# k1fm-pico-balloon-v1_3.net
KiCad netlist of a schematic drawn in EAGLE
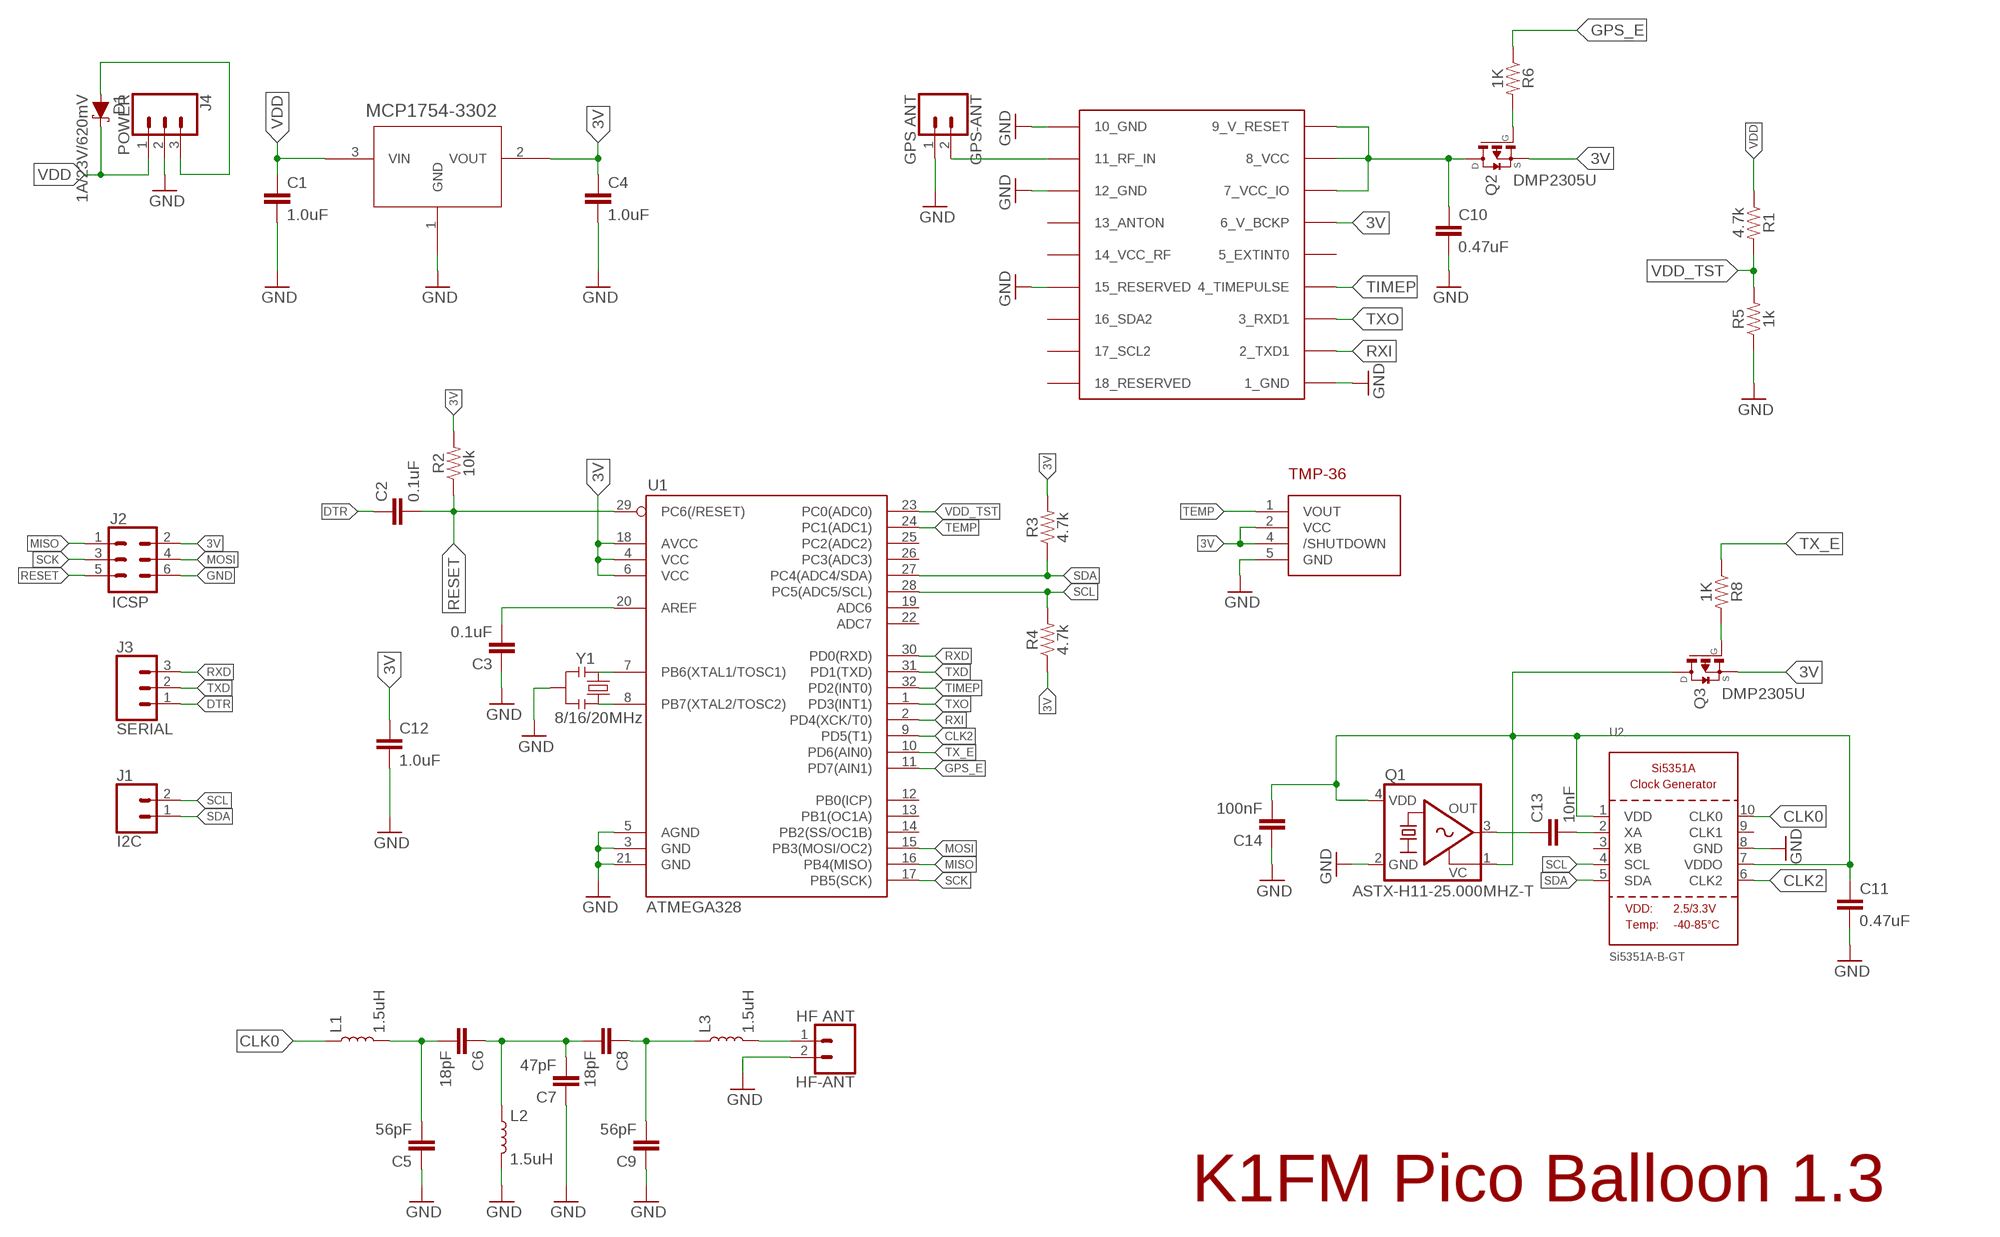
[diagram p0: schematic, sheet 1]

(export (version "E")
  (design (tool "Eeschema 10.0.6"))
  (components
    (comp (ref "C1")
      (value "1.0uF")
      (footprint "eagle-import:0603")
      (libsource (lib "eagle-import") (part "1.0UF-0603-16V-10%"))
    )
    (comp (ref "C2")
      (value "0.1uF")
      (footprint "eagle-import:0603")
      (libsource (lib "eagle-import") (part "0.1UF-0603-25V-5%"))
    )
    (comp (ref "C3")
      (value "0.1uF")
      (footprint "eagle-import:0603")
      (libsource (lib "eagle-import") (part "0.1UF-0603-25V-5%"))
    )
    (comp (ref "C4")
      (value "1.0uF")
      (footprint "eagle-import:0603")
      (libsource (lib "eagle-import") (part "1.0UF-0603-16V-10%"))
    )
    (comp (ref "C5")
      (value "56pF")
      (footprint "eagle-import:0603")
      (libsource (lib "eagle-import") (part "0.1UF-0603-25V-5%"))
    )
    (comp (ref "C6")
      (value "18pF")
      (footprint "eagle-import:0603")
      (libsource (lib "eagle-import") (part "0.1UF-0603-25V-5%"))
    )
    (comp (ref "C7")
      (value "47pF")
      (footprint "eagle-import:0603")
      (libsource (lib "eagle-import") (part "0.1UF-0603-25V-5%"))
    )
    (comp (ref "C8")
      (value "18pF")
      (footprint "eagle-import:0603")
      (libsource (lib "eagle-import") (part "0.1UF-0603-25V-5%"))
    )
    (comp (ref "C9")
      (value "56pF")
      (footprint "eagle-import:0603")
      (libsource (lib "eagle-import") (part "0.1UF-0603-25V-5%"))
    )
    (comp (ref "C10")
      (value "0.47uF")
      (footprint "eagle-import:0603")
      (libsource (lib "eagle-import") (part "0.1UF-0603-25V-5%"))
    )
    (comp (ref "C11")
      (value "0.47uF")
      (footprint "eagle-import:0603")
      (libsource (lib "eagle-import") (part "0.1UF-0603-25V-5%"))
    )
    (comp (ref "C12")
      (value "1.0uF")
      (footprint "eagle-import:0603")
      (libsource (lib "eagle-import") (part "1.0UF-0603-16V-10%"))
    )
    (comp (ref "C13")
      (value "10nF")
      (footprint "eagle-import:0603")
      (libsource (lib "eagle-import") (part "10NF-0603-50V-10%"))
    )
    (comp (ref "C14")
      (value "100nF")
      (footprint "eagle-import:0603")
      (libsource (lib "eagle-import") (part "10NF-0603-50V-10%"))
    )
    (comp (ref "D1")
      (value "1A/23V/620mV")
      (footprint "eagle-import:SOD-323")
      (libsource (lib "eagle-import") (part "DIODE-SCHOTTKY-BAT20J"))
    )
    (comp (ref "GPS-ANT")
      (value "GPS ANT")
      (footprint "eagle-import:1X02")
      (libsource (lib "eagle-import") (part "CONN_02"))
    )
    (comp (ref "GPS1")
      (value "UBLOX_MAX")
      (footprint "eagle-import:UBLOX_MAX")
      (libsource (lib "eagle-import") (part "UBLOX_MAX"))
    )
    (comp (ref "HF-ANT")
      (value "HF ANT")
      (footprint "eagle-import:1X02")
      (libsource (lib "eagle-import") (part "CONN_02"))
    )
    (comp (ref "J1")
      (value "I2C")
      (footprint "eagle-import:1X02")
      (libsource (lib "eagle-import") (part "CONN_02"))
    )
    (comp (ref "J2")
      (value "ICSP")
      (footprint "eagle-import:2X3")
      (libsource (lib "eagle-import") (part "CONN_03X2FEMALE"))
    )
    (comp (ref "J3")
      (value "SERIAL")
      (footprint "eagle-import:1X03")
      (libsource (lib "eagle-import") (part "CONN_03"))
    )
    (comp (ref "J4")
      (value "POWER")
      (footprint "eagle-import:1X03")
      (libsource (lib "eagle-import") (part "CONN_03"))
    )
    (comp (ref "L1")
      (value "1.5uH")
      (footprint "eagle-import:0603")
      (libsource (lib "eagle-import") (part "INDUCTOR-0603-33NH"))
    )
    (comp (ref "L2")
      (value "1.5uH")
      (footprint "eagle-import:0603")
      (libsource (lib "eagle-import") (part "INDUCTOR-0603-33NH"))
    )
    (comp (ref "L3")
      (value "1.5uH")
      (footprint "eagle-import:0603")
      (libsource (lib "eagle-import") (part "INDUCTOR-0603-33NH"))
    )
    (comp (ref "Q1")
      (value "ASTX-H11-25.000MHZ-T")
      (footprint "eagle-import:3.2X2.5_KXO-84")
      (libsource (lib "eagle-import") (part "KXO-VCXO-SINE-84"))
    )
    (comp (ref "Q2")
      (value "DMP2305U")
      (footprint "eagle-import:SOT23")
      (libsource (lib "eagle-import") (part "DMP2305U"))
    )
    (comp (ref "Q3")
      (value "DMP2305U")
      (footprint "eagle-import:SOT23")
      (libsource (lib "eagle-import") (part "DMP2305U"))
    )
    (comp (ref "R1")
      (value "4.7k")
      (footprint "eagle-import:0603")
      (libsource (lib "eagle-import") (part "10KOHM-0603-1/10W-1%"))
    )
    (comp (ref "R2")
      (value "10k")
      (footprint "eagle-import:0603")
      (libsource (lib "eagle-import") (part "10KOHM-0603-1/10W-1%"))
    )
    (comp (ref "R3")
      (value "4.7k")
      (footprint "eagle-import:0603")
      (libsource (lib "eagle-import") (part "4.7KOHM-0603-1/10W-1%"))
    )
    (comp (ref "R4")
      (value "4.7k")
      (footprint "eagle-import:0603")
      (libsource (lib "eagle-import") (part "4.7KOHM-0603-1/10W-1%"))
    )
    (comp (ref "R5")
      (value "1k")
      (footprint "eagle-import:0603")
      (libsource (lib "eagle-import") (part "10KOHM-0603-1/10W-1%"))
    )
    (comp (ref "R6")
      (value "1K")
      (footprint "eagle-import:0603")
      (libsource (lib "eagle-import") (part "10KOHM-0603-1/10W-1%"))
    )
    (comp (ref "R8")
      (value "1K")
      (footprint "eagle-import:0603")
      (libsource (lib "eagle-import") (part "10KOHM-0603-1/10W-1%"))
    )
    (comp (ref "U1")
      (value "ATMEGA328")
      (footprint "eagle-import:TQFP32-08")
      (libsource (lib "eagle-import") (part "ATMEGA168"))
    )
    (comp (ref "U2")
      (value "Si5351A-B-GT")
      (footprint "eagle-import:MSOP10")
      (libsource (lib "eagle-import") (part "SI5351A"))
    )
    (comp (ref "U3")
      (value "MCP1754X-XXXXX/C")
      (footprint "eagle-import:SOT-23A_MC")
      (libsource (lib "eagle-import") (part "MCP1754X-XXXXX/C"))
    )
    (comp (ref "U4")
      (value "TMP36")
      (footprint "eagle-import:SOT-23")
      (libsource (lib "eagle-import") (part "TMP36"))
    )
    (comp (ref "Y1")
      (value "8/16/20MHz")
      (footprint "eagle-import:RESONATOR-SMD-1_1")
      (libsource (lib "eagle-import") (part "RESONATOR1{colon}1"))
    )
  )
  (nets
    (net (code "1") (name "3V") (class "Default")
      (node (ref "C12") (pin "1") (pinfunction "1_1") (pintype "passive"))
      (node (ref "C4") (pin "1") (pinfunction "1_1") (pintype "passive"))
      (node (ref "GPS1") (pin "6_V_BCKP") (pinfunction "6_V_BCKP_6_V_BCKP") (pintype "bidirectional"))
      (node (ref "J2") (pin "2") (pinfunction "2_2") (pintype "bidirectional"))
      (node (ref "Q2") (pin "2") (pinfunction "S_2") (pintype "passive"))
      (node (ref "Q3") (pin "2") (pinfunction "S_2") (pintype "passive"))
      (node (ref "R2") (pin "2") (pinfunction "2_2") (pintype "passive"))
      (node (ref "R3") (pin "2") (pinfunction "2_2") (pintype "passive"))
      (node (ref "R4") (pin "1") (pinfunction "1_1") (pintype "passive"))
      (node (ref "U1") (pin "18") (pinfunction "AVCC_18") (pintype "bidirectional"))
      (node (ref "U1") (pin "4") (pinfunction "VCC_4") (pintype "bidirectional"))
      (node (ref "U1") (pin "6") (pinfunction "VCC_6") (pintype "bidirectional"))
      (node (ref "U3") (pin "2") (pinfunction "VOUT_2") (pintype "passive"))
      (node (ref "U4") (pin "2") (pinfunction "VCC_2") (pintype "bidirectional"))
      (node (ref "U4") (pin "4") (pinfunction "/SHUTDOWN_4") (pintype "bidirectional"))
    )
    (net (code "2") (name "CLK0") (class "Default")
      (node (ref "L1") (pin "1") (pinfunction "1_1") (pintype "passive"))
      (node (ref "U2") (pin "10") (pinfunction "CLK0_10") (pintype "output"))
    )
    (net (code "3") (name "CLK2") (class "Default")
      (node (ref "U1") (pin "9") (pinfunction "PD5(T1)_9") (pintype "bidirectional"))
      (node (ref "U2") (pin "6") (pinfunction "CLK2_6") (pintype "output"))
    )
    (net (code "4") (name "DTR") (class "Default")
      (node (ref "C2") (pin "1") (pinfunction "1_1") (pintype "passive"))
      (node (ref "J3") (pin "1") (pinfunction "1_1") (pintype "passive"))
    )
    (net (code "5") (name "GND") (class "Default")
      (node (ref "C1") (pin "2") (pinfunction "2_2") (pintype "passive"))
      (node (ref "C10") (pin "2") (pinfunction "2_2") (pintype "passive"))
      (node (ref "C11") (pin "2") (pinfunction "2_2") (pintype "passive"))
      (node (ref "C12") (pin "2") (pinfunction "2_2") (pintype "passive"))
      (node (ref "C14") (pin "1") (pinfunction "1_1") (pintype "passive"))
      (node (ref "C3") (pin "1") (pinfunction "1_1") (pintype "passive"))
      (node (ref "C4") (pin "2") (pinfunction "2_2") (pintype "passive"))
      (node (ref "C5") (pin "1") (pinfunction "1_1") (pintype "passive"))
      (node (ref "C7") (pin "1") (pinfunction "1_1") (pintype "passive"))
      (node (ref "C9") (pin "1") (pinfunction "1_1") (pintype "passive"))
      (node (ref "GPS-ANT") (pin "1") (pinfunction "1_1") (pintype "passive"))
      (node (ref "GPS1") (pin "10_GND") (pinfunction "10_GND_10_GND") (pintype "power_in"))
      (node (ref "GPS1") (pin "12_GND") (pinfunction "12_GND_12_GND") (pintype "power_in"))
      (node (ref "GPS1") (pin "15_RESERVED") (pinfunction "15_RESERVED_15_RESERVED") (pintype "bidirectional"))
      (node (ref "GPS1") (pin "1_GND") (pinfunction "1_GND_1_GND") (pintype "power_in"))
      (node (ref "HF-ANT") (pin "2") (pinfunction "2_2") (pintype "passive"))
      (node (ref "J2") (pin "6") (pinfunction "6_6") (pintype "bidirectional"))
      (node (ref "J4") (pin "2") (pinfunction "2_2") (pintype "passive"))
      (node (ref "L2") (pin "2") (pinfunction "2_2") (pintype "passive"))
      (node (ref "Q1") (pin "2") (pinfunction "GND_2") (pintype "power_in"))
      (node (ref "R5") (pin "1") (pinfunction "1_1") (pintype "passive"))
      (node (ref "U1") (pin "21") (pinfunction "GND_21") (pintype "bidirectional"))
      (node (ref "U1") (pin "3") (pinfunction "GND_3") (pintype "bidirectional"))
      (node (ref "U1") (pin "5") (pinfunction "AGND_5") (pintype "bidirectional"))
      (node (ref "U2") (pin "8") (pinfunction "GND_8") (pintype "power_in"))
      (node (ref "U3") (pin "1") (pinfunction "GND_1") (pintype "passive"))
      (node (ref "U4") (pin "5") (pinfunction "GND_5") (pintype "bidirectional"))
      (node (ref "Y1") (pin "2") (pinfunction "2_2") (pintype "passive"))
    )
    (net (code "6") (name "GPS_E") (class "Default")
      (node (ref "R6") (pin "1") (pinfunction "1_1") (pintype "passive"))
      (node (ref "U1") (pin "11") (pinfunction "PD7(AIN1)_11") (pintype "bidirectional"))
    )
    (net (code "7") (name "MISO") (class "Default")
      (node (ref "J2") (pin "1") (pinfunction "1_1") (pintype "bidirectional"))
      (node (ref "U1") (pin "16") (pinfunction "PB4(MISO)_16") (pintype "bidirectional"))
    )
    (net (code "8") (name "MOSI") (class "Default")
      (node (ref "J2") (pin "4") (pinfunction "4_4") (pintype "bidirectional"))
      (node (ref "U1") (pin "15") (pinfunction "PB3(MOSI/OC2)_15") (pintype "bidirectional"))
    )
    (net (code "9") (name "Net-(C5-Pad2)") (class "Default")
      (node (ref "C5") (pin "2") (pinfunction "2_2") (pintype "passive"))
      (node (ref "C6") (pin "2") (pinfunction "2_2") (pintype "passive"))
      (node (ref "L1") (pin "2") (pinfunction "2_2") (pintype "passive"))
    )
    (net (code "10") (name "Net-(C6-Pad1)") (class "Default")
      (node (ref "C6") (pin "1") (pinfunction "1_1") (pintype "passive"))
      (node (ref "C7") (pin "2") (pinfunction "2_2") (pintype "passive"))
      (node (ref "C8") (pin "2") (pinfunction "2_2") (pintype "passive"))
      (node (ref "L2") (pin "1") (pinfunction "1_1") (pintype "passive"))
    )
    (net (code "11") (name "Net-(C8-Pad1)") (class "Default")
      (node (ref "C8") (pin "1") (pinfunction "1_1") (pintype "passive"))
      (node (ref "C9") (pin "2") (pinfunction "2_2") (pintype "passive"))
      (node (ref "L3") (pin "1") (pinfunction "1_1") (pintype "passive"))
    )
    (net (code "12") (name "Net-(D1-PadA)") (class "Default")
      (node (ref "D1") (pin "A") (pinfunction "A_A") (pintype "passive"))
      (node (ref "J4") (pin "3") (pinfunction "3_3") (pintype "passive"))
    )
    (net (code "13") (name "Net-(GPS-ANT-Pad2)") (class "Default")
      (node (ref "GPS-ANT") (pin "2") (pinfunction "2_2") (pintype "passive"))
      (node (ref "GPS1") (pin "11_RF_IN") (pinfunction "11_RF_IN_11_RF_IN") (pintype "bidirectional"))
    )
    (net (code "14") (name "Net-(HF-ANT-Pad1)") (class "Default")
      (node (ref "HF-ANT") (pin "1") (pinfunction "1_1") (pintype "passive"))
      (node (ref "L3") (pin "2") (pinfunction "2_2") (pintype "passive"))
    )
    (net (code "15") (name "Net-(Q1-OUT)") (class "Default")
      (node (ref "C13") (pin "1") (pinfunction "1_1") (pintype "passive"))
      (node (ref "Q1") (pin "3") (pinfunction "OUT_3") (pintype "output"))
    )
    (net (code "16") (name "Net-(Q1-VC)") (class "Default")
      (node (ref "C11") (pin "1") (pinfunction "1_1") (pintype "passive"))
      (node (ref "C14") (pin "2") (pinfunction "2_2") (pintype "passive"))
      (node (ref "Q1") (pin "1") (pinfunction "VC_1") (pintype "input"))
      (node (ref "Q1") (pin "4") (pinfunction "VDD_4") (pintype "power_in"))
      (node (ref "Q3") (pin "3") (pinfunction "D_3") (pintype "passive"))
      (node (ref "U2") (pin "1") (pinfunction "VDD_1") (pintype "power_in"))
      (node (ref "U2") (pin "7") (pinfunction "VDDO_7") (pintype "power_in"))
    )
    (net (code "17") (name "Net-(Q2-D)") (class "Default")
      (node (ref "C10") (pin "1") (pinfunction "1_1") (pintype "passive"))
      (node (ref "GPS1") (pin "7_VCC_IO") (pinfunction "7_VCC_IO_7_VCC_IO") (pintype "power_in"))
      (node (ref "GPS1") (pin "8_VCC") (pinfunction "8_VCC_8_VCC") (pintype "power_in"))
      (node (ref "GPS1") (pin "9_V_RESET") (pinfunction "9_V_RESET_9_V_RESET") (pintype "power_in"))
      (node (ref "Q2") (pin "3") (pinfunction "D_3") (pintype "passive"))
    )
    (net (code "18") (name "Net-(Q2-G)") (class "Default")
      (node (ref "Q2") (pin "1") (pinfunction "G_1") (pintype "passive"))
      (node (ref "R6") (pin "2") (pinfunction "2_2") (pintype "passive"))
    )
    (net (code "19") (name "Net-(Q3-G)") (class "Default")
      (node (ref "Q3") (pin "1") (pinfunction "G_1") (pintype "passive"))
      (node (ref "R8") (pin "2") (pinfunction "2_2") (pintype "passive"))
    )
    (net (code "20") (name "Net-(U1-AREF)") (class "Default")
      (node (ref "C3") (pin "2") (pinfunction "2_2") (pintype "passive"))
      (node (ref "U1") (pin "20") (pinfunction "AREF_20") (pintype "bidirectional"))
    )
    (net (code "21") (name "Net-(U1-PB6(XTAL1{slash}TOSC1))") (class "Default")
      (node (ref "U1") (pin "7") (pinfunction "PB6(XTAL1/TOSC1)_7") (pintype "bidirectional"))
      (node (ref "Y1") (pin "1") (pinfunction "1_1") (pintype "passive"))
    )
    (net (code "22") (name "Net-(U1-PB7(XTAL2{slash}TOSC2))") (class "Default")
      (node (ref "U1") (pin "8") (pinfunction "PB7(XTAL2/TOSC2)_8") (pintype "bidirectional"))
      (node (ref "Y1") (pin "3") (pinfunction "3_3") (pintype "passive"))
    )
    (net (code "23") (name "Net-(U2-XA)") (class "Default")
      (node (ref "C13") (pin "2") (pinfunction "2_2") (pintype "passive"))
      (node (ref "U2") (pin "2") (pinfunction "XA_2") (pintype "input"))
    )
    (net (code "24") (name "RESET") (class "Default")
      (node (ref "C2") (pin "2") (pinfunction "2_2") (pintype "passive"))
      (node (ref "J2") (pin "5") (pinfunction "5_5") (pintype "bidirectional"))
      (node (ref "R2") (pin "1") (pinfunction "1_1") (pintype "passive"))
      (node (ref "U1") (pin "29") (pinfunction "PC6(/RESET)_29") (pintype "bidirectional"))
    )
    (net (code "25") (name "RXD") (class "Default")
      (node (ref "J3") (pin "3") (pinfunction "3_3") (pintype "passive"))
      (node (ref "U1") (pin "30") (pinfunction "PD0(RXD)_30") (pintype "bidirectional"))
    )
    (net (code "26") (name "RXI") (class "Default")
      (node (ref "GPS1") (pin "2_TXD1") (pinfunction "2_TXD1_2_TXD1") (pintype "bidirectional"))
      (node (ref "U1") (pin "2") (pinfunction "PD4(XCK/T0)_2") (pintype "bidirectional"))
    )
    (net (code "27") (name "SCK") (class "Default")
      (node (ref "J2") (pin "3") (pinfunction "3_3") (pintype "bidirectional"))
      (node (ref "U1") (pin "17") (pinfunction "PB5(SCK)_17") (pintype "bidirectional"))
    )
    (net (code "28") (name "SCL") (class "Default")
      (node (ref "J1") (pin "2") (pinfunction "2_2") (pintype "passive"))
      (node (ref "R4") (pin "2") (pinfunction "2_2") (pintype "passive"))
      (node (ref "U1") (pin "28") (pinfunction "PC5(ADC5/SCL)_28") (pintype "bidirectional"))
      (node (ref "U2") (pin "4") (pinfunction "SCL_4") (pintype "input"))
    )
    (net (code "29") (name "SDA") (class "Default")
      (node (ref "J1") (pin "1") (pinfunction "1_1") (pintype "passive"))
      (node (ref "R3") (pin "1") (pinfunction "1_1") (pintype "passive"))
      (node (ref "U1") (pin "27") (pinfunction "PC4(ADC4/SDA)_27") (pintype "bidirectional"))
      (node (ref "U2") (pin "5") (pinfunction "SDA_5") (pintype "bidirectional"))
    )
    (net (code "30") (name "TEMP") (class "Default")
      (node (ref "U1") (pin "24") (pinfunction "PC1(ADC1)_24") (pintype "bidirectional"))
      (node (ref "U4") (pin "1") (pinfunction "VOUT_1") (pintype "bidirectional"))
    )
    (net (code "31") (name "TIMEP") (class "Default")
      (node (ref "GPS1") (pin "4_TIMEPULSE") (pinfunction "4_TIMEPULSE_4_TIMEPULSE") (pintype "bidirectional"))
      (node (ref "U1") (pin "32") (pinfunction "PD2(INT0)_32") (pintype "bidirectional"))
    )
    (net (code "32") (name "TXD") (class "Default")
      (node (ref "J3") (pin "2") (pinfunction "2_2") (pintype "passive"))
      (node (ref "U1") (pin "31") (pinfunction "PD1(TXD)_31") (pintype "bidirectional"))
    )
    (net (code "33") (name "TXO") (class "Default")
      (node (ref "GPS1") (pin "3_RXD1") (pinfunction "3_RXD1_3_RXD1") (pintype "bidirectional"))
      (node (ref "U1") (pin "1") (pinfunction "PD3(INT1)_1") (pintype "bidirectional"))
    )
    (net (code "34") (name "TX_E") (class "Default")
      (node (ref "R8") (pin "1") (pinfunction "1_1") (pintype "passive"))
      (node (ref "U1") (pin "10") (pinfunction "PD6(AIN0)_10") (pintype "bidirectional"))
    )
    (net (code "35") (name "VDD") (class "Default")
      (node (ref "C1") (pin "1") (pinfunction "1_1") (pintype "passive"))
      (node (ref "D1") (pin "C") (pinfunction "C_C") (pintype "passive"))
      (node (ref "J4") (pin "1") (pinfunction "1_1") (pintype "passive"))
      (node (ref "R1") (pin "1") (pinfunction "1_1") (pintype "passive"))
      (node (ref "U3") (pin "3") (pinfunction "VIN_3") (pintype "passive"))
    )
    (net (code "36") (name "VDD_TST") (class "Default")
      (node (ref "R1") (pin "2") (pinfunction "2_2") (pintype "passive"))
      (node (ref "R5") (pin "2") (pinfunction "2_2") (pintype "passive"))
      (node (ref "U1") (pin "23") (pinfunction "PC0(ADC0)_23") (pintype "bidirectional"))
    )
    (net (code "37") (name "unconnected-(GPS1-Pad5_EXTINT0)") (class "Default")
      (node (ref "GPS1") (pin "5_EXTINT0") (pinfunction "5_EXTINT0_5_EXTINT0") (pintype "bidirectional"))
    )
    (net (code "38") (name "unconnected-(GPS1-Pad13_ANTON)") (class "Default")
      (node (ref "GPS1") (pin "13_ANTON") (pinfunction "13_ANTON_13_ANTON") (pintype "bidirectional"))
    )
    (net (code "39") (name "unconnected-(GPS1-Pad14_VCC_RF)") (class "Default")
      (node (ref "GPS1") (pin "14_VCC_RF") (pinfunction "14_VCC_RF_14_VCC_RF") (pintype "bidirectional"))
    )
    (net (code "40") (name "unconnected-(GPS1-Pad16_SDA2)") (class "Default")
      (node (ref "GPS1") (pin "16_SDA2") (pinfunction "16_SDA2_16_SDA2") (pintype "bidirectional"))
    )
    (net (code "41") (name "unconnected-(GPS1-Pad17_SCL2)") (class "Default")
      (node (ref "GPS1") (pin "17_SCL2") (pinfunction "17_SCL2_17_SCL2") (pintype "bidirectional"))
    )
    (net (code "42") (name "unconnected-(GPS1-Pad18_RESERVED)") (class "Default")
      (node (ref "GPS1") (pin "18_RESERVED") (pinfunction "18_RESERVED_18_RESERVED") (pintype "bidirectional"))
    )
    (net (code "43") (name "unconnected-(U1-ADC6-Pad19)") (class "Default")
      (node (ref "U1") (pin "19") (pinfunction "ADC6_19") (pintype "bidirectional"))
    )
    (net (code "44") (name "unconnected-(U1-ADC7-Pad22)") (class "Default")
      (node (ref "U1") (pin "22") (pinfunction "ADC7_22") (pintype "bidirectional"))
    )
    (net (code "45") (name "unconnected-(U1-PB0(ICP)-Pad12)") (class "Default")
      (node (ref "U1") (pin "12") (pinfunction "PB0(ICP)_12") (pintype "bidirectional"))
    )
    (net (code "46") (name "unconnected-(U1-PB1(OC1A)-Pad13)") (class "Default")
      (node (ref "U1") (pin "13") (pinfunction "PB1(OC1A)_13") (pintype "bidirectional"))
    )
    (net (code "47") (name "unconnected-(U1-PB2(SS{slash}OC1B)-Pad14)") (class "Default")
      (node (ref "U1") (pin "14") (pinfunction "PB2(SS/OC1B)_14") (pintype "bidirectional"))
    )
    (net (code "48") (name "unconnected-(U1-PC2(ADC2)-Pad25)") (class "Default")
      (node (ref "U1") (pin "25") (pinfunction "PC2(ADC2)_25") (pintype "bidirectional"))
    )
    (net (code "49") (name "unconnected-(U1-PC3(ADC3)-Pad26)") (class "Default")
      (node (ref "U1") (pin "26") (pinfunction "PC3(ADC3)_26") (pintype "bidirectional"))
    )
    (net (code "50") (name "unconnected-(U2-CLK1-Pad9)") (class "Default")
      (node (ref "U2") (pin "9") (pinfunction "CLK1_9") (pintype "output"))
    )
    (net (code "51") (name "unconnected-(U2-XB-Pad3)") (class "Default")
      (node (ref "U2") (pin "3") (pinfunction "XB_3") (pintype "input"))
    )
  )
)
